# Side_ShortE.net
KiCad netlist of a schematic drawn in EAGLE
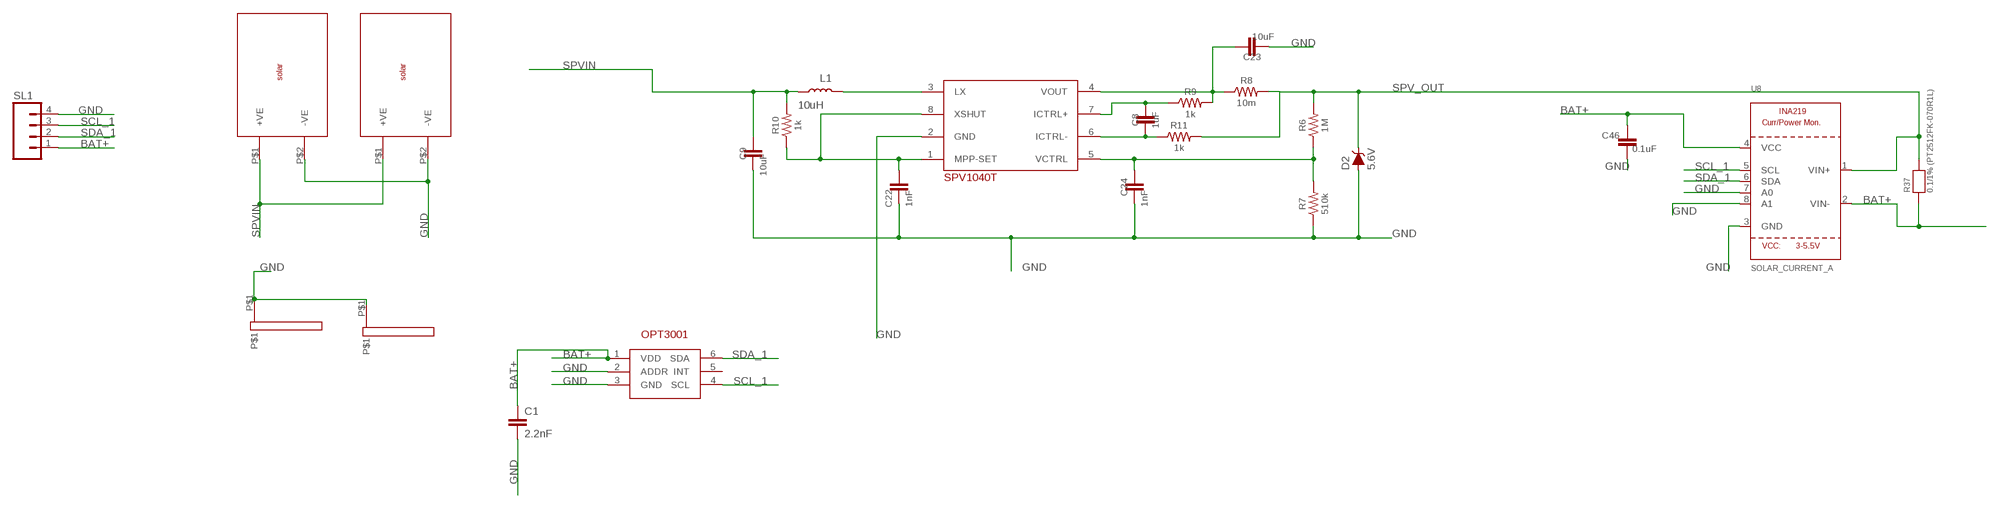
[diagram p0: schematic, sheet 1]

(export (version "E")
  (design (tool "Eeschema 10.0.6"))
  (components
    (comp (ref "C1")
      (value "2.2nF")
      (footprint "eagle-import:0603")
      (libsource (lib "eagle-import") (part "2.2NF/2200PF-0603-50V-10%"))
    )
    (comp (ref "C8")
      (value "1uF")
      (footprint "eagle-import:0603")
      (libsource (lib "eagle-import") (part "10UF-0603-6.3V-20%"))
    )
    (comp (ref "C9")
      (value "10uF")
      (footprint "eagle-import:0603")
      (libsource (lib "eagle-import") (part "10UF-0603-6.3V-20%"))
    )
    (comp (ref "C22")
      (value "1nF")
      (footprint "eagle-import:0603")
      (libsource (lib "eagle-import") (part "10UF-0603-6.3V-20%"))
    )
    (comp (ref "C23")
      (value "10uF")
      (footprint "eagle-import:0603")
      (libsource (lib "eagle-import") (part "10UF-0603-6.3V-20%"))
    )
    (comp (ref "C24")
      (value "1nF")
      (footprint "eagle-import:0603")
      (libsource (lib "eagle-import") (part "10UF-0603-6.3V-20%"))
    )
    (comp (ref "C46")
      (value "0.1uF")
      (footprint "eagle-import:0603")
      (libsource (lib "eagle-import") (part "10UF-0603-6.3V-20%"))
    )
    (comp (ref "D2")
      (value "5.6V")
      (footprint "eagle-import:SOD-323")
      (libsource (lib "eagle-import") (part "DIODE-ZENER-MMSZ5232BS"))
    )
    (comp (ref "L1")
      (value "10uH")
      (footprint "eagle-import:0603")
      (libsource (lib "eagle-import") (part "INDUCTOR-0603-33NH"))
    )
    (comp (ref "R6")
      (value "1M")
      (footprint "eagle-import:RES_0603")
      (fields
        (field (name "DIGIKEY_PART_NUMBER") "311-0.0GRTR-ND")
        (field (name "MANUFACTURER") "Yageo")
        (field (name "MPN") "RC0603JR-070RL")
        (field (name "CREATED_BY") "PCBLayout.com")
      )
      (libsource (lib "eagle-import") (part "RC0603JR-070RL"))
    )
    (comp (ref "R7")
      (value "510k")
      (footprint "eagle-import:RES_0603")
      (fields
        (field (name "DIGIKEY_PART_NUMBER") "311-0.0GRTR-ND")
        (field (name "MANUFACTURER") "Yageo")
        (field (name "MPN") "RC0603JR-070RL")
        (field (name "CREATED_BY") "PCBLayout.com")
      )
      (libsource (lib "eagle-import") (part "RC0603JR-070RL"))
    )
    (comp (ref "R8")
      (value "10m")
      (footprint "eagle-import:RES_0603")
      (fields
        (field (name "DIGIKEY_PART_NUMBER") "311-0.0GRTR-ND")
        (field (name "MANUFACTURER") "Yageo")
        (field (name "MPN") "RC0603JR-070RL")
        (field (name "CREATED_BY") "PCBLayout.com")
      )
      (libsource (lib "eagle-import") (part "RC0603JR-070RL"))
    )
    (comp (ref "R9")
      (value "1k")
      (footprint "eagle-import:RES_0603")
      (fields
        (field (name "DIGIKEY_PART_NUMBER") "311-0.0GRTR-ND")
        (field (name "MANUFACTURER") "Yageo")
        (field (name "MPN") "RC0603JR-070RL")
        (field (name "CREATED_BY") "PCBLayout.com")
      )
      (libsource (lib "eagle-import") (part "RC0603JR-070RL"))
    )
    (comp (ref "R10")
      (value "1k")
      (footprint "eagle-import:RES_0603")
      (fields
        (field (name "DIGIKEY_PART_NUMBER") "311-0.0GRTR-ND")
        (field (name "MANUFACTURER") "Yageo")
        (field (name "MPN") "RC0603JR-070RL")
        (field (name "CREATED_BY") "PCBLayout.com")
      )
      (libsource (lib "eagle-import") (part "RC0603JR-070RL"))
    )
    (comp (ref "R11")
      (value "1k")
      (footprint "eagle-import:RES_0603")
      (fields
        (field (name "DIGIKEY_PART_NUMBER") "311-0.0GRTR-ND")
        (field (name "MANUFACTURER") "Yageo")
        (field (name "MPN") "RC0603JR-070RL")
        (field (name "CREATED_BY") "PCBLayout.com")
      )
      (libsource (lib "eagle-import") (part "RC0603JR-070RL"))
    )
    (comp (ref "R37")
      (value "0.1/1% (PT2512FK-070R1L)")
      (footprint "eagle-import:2512")
      (libsource (lib "eagle-import") (part "RESISTOR2512"))
    )
    (comp (ref "SL1")
      (value "M04")
      (footprint "eagle-import:04P")
      (libsource (lib "eagle-import") (part "M04"))
    )
    (comp (ref "SPV_A")
      (value "SPV1040T_")
      (footprint "eagle-import:SOP65P640X120-8N")
      (libsource (lib "eagle-import") (part "SPV1040T_"))
    )
    (comp (ref "U$1")
      (value "16X2")
      (footprint "eagle-import:16X2")
      (libsource (lib "eagle-import") (part "16X2"))
    )
    (comp (ref "U$2")
      (value "16X2")
      (footprint "eagle-import:16X2")
      (libsource (lib "eagle-import") (part "16X2"))
    )
    (comp (ref "U$3")
      (value "SOLAR_50_5_2")
      (footprint "eagle-import:FOOT")
      (libsource (lib "eagle-import") (part "SOLAR_50_5_2"))
    )
    (comp (ref "U$4")
      (value "SOLAR_50_5_2")
      (footprint "eagle-import:FOOT")
      (libsource (lib "eagle-import") (part "SOLAR_50_5_2"))
    )
    (comp (ref "U1")
      (value "SON65P200X200X65-7N")
      (footprint "eagle-import:SON65P200X200X65-7N")
      (fields (field (name "MANUFACTURER") "Maxim Integrated"))
      (libsource (lib "eagle-import") (part "SON65P200X200X65-7N"))
    )
    (comp (ref "U8")
      (value "SOLAR_CURRENT_A")
      (footprint "eagle-import:SOT23-8")
      (libsource (lib "eagle-import") (part "INA219"))
    )
  )
  (nets
    (net (code "1") (name "/BAT+") (class "Default")
      (node (ref "C1") (pin "1") (pinfunction "1_1") (pintype "passive"))
      (node (ref "C46") (pin "1") (pinfunction "1_1") (pintype "passive"))
      (node (ref "R37") (pin "1") (pinfunction "1_1") (pintype "passive"))
      (node (ref "SL1") (pin "1") (pinfunction "1_1") (pintype "passive"))
      (node (ref "U1") (pin "1") (pinfunction "VDD_1") (pintype "bidirectional"))
      (node (ref "U8") (pin "2") (pinfunction "VIN-_2") (pintype "bidirectional"))
      (node (ref "U8") (pin "4") (pinfunction "VCC_4") (pintype "bidirectional"))
    )
    (net (code "2") (name "/GND") (class "Default")
      (node (ref "C1") (pin "2") (pinfunction "2_2") (pintype "passive"))
      (node (ref "C22") (pin "2") (pinfunction "2_2") (pintype "passive"))
      (node (ref "C23") (pin "2") (pinfunction "2_2") (pintype "passive"))
      (node (ref "C24") (pin "2") (pinfunction "2_2") (pintype "passive"))
      (node (ref "C46") (pin "2") (pinfunction "2_2") (pintype "passive"))
      (node (ref "C9") (pin "2") (pinfunction "2_2") (pintype "passive"))
      (node (ref "D2") (pin "A") (pinfunction "A_A") (pintype "passive"))
      (node (ref "R7") (pin "1") (pinfunction "1_1") (pintype "passive"))
      (node (ref "SL1") (pin "4") (pinfunction "4_4") (pintype "passive"))
      (node (ref "SPV_A") (pin "2") (pinfunction "GND_2") (pintype "bidirectional"))
      (node (ref "U$1") (pin "P$1") (pinfunction "P$1_P$1") (pintype "bidirectional"))
      (node (ref "U$2") (pin "P$1") (pinfunction "P$1_P$1") (pintype "bidirectional"))
      (node (ref "U$3") (pin "P$2") (pinfunction "-VE_P$2") (pintype "bidirectional"))
      (node (ref "U$4") (pin "P$2") (pinfunction "-VE_P$2") (pintype "bidirectional"))
      (node (ref "U1") (pin "2") (pinfunction "ADDR_2") (pintype "bidirectional"))
      (node (ref "U1") (pin "3") (pinfunction "GND_3") (pintype "bidirectional"))
      (node (ref "U8") (pin "3") (pinfunction "GND_3") (pintype "bidirectional"))
      (node (ref "U8") (pin "7") (pinfunction "A0_7") (pintype "bidirectional"))
      (node (ref "U8") (pin "8") (pinfunction "A1_8") (pintype "bidirectional"))
    )
    (net (code "3") (name "/SCL_1") (class "Default")
      (node (ref "SL1") (pin "3") (pinfunction "3_3") (pintype "passive"))
      (node (ref "U1") (pin "4") (pinfunction "SCL_4") (pintype "bidirectional"))
      (node (ref "U8") (pin "5") (pinfunction "SCL_5") (pintype "bidirectional"))
    )
    (net (code "4") (name "/SDA_1") (class "Default")
      (node (ref "SL1") (pin "2") (pinfunction "2_2") (pintype "passive"))
      (node (ref "U1") (pin "6") (pinfunction "SDA_6") (pintype "bidirectional"))
      (node (ref "U8") (pin "6") (pinfunction "SDA_6") (pintype "bidirectional"))
    )
    (net (code "5") (name "/SPVIN") (class "Default")
      (node (ref "C9") (pin "1") (pinfunction "1_1") (pintype "passive"))
      (node (ref "L1") (pin "1") (pinfunction "1_1") (pintype "passive"))
      (node (ref "R10") (pin "2") (pinfunction "2_2") (pintype "passive"))
      (node (ref "U$3") (pin "P$1") (pinfunction "+VE_P$1") (pintype "bidirectional"))
      (node (ref "U$4") (pin "P$1") (pinfunction "+VE_P$1") (pintype "bidirectional"))
    )
    (net (code "6") (name "/SPV_OUT") (class "Default")
      (node (ref "D2") (pin "C") (pinfunction "C_C") (pintype "passive"))
      (node (ref "R11") (pin "2") (pinfunction "2_2") (pintype "passive"))
      (node (ref "R37") (pin "2") (pinfunction "2_2") (pintype "passive"))
      (node (ref "R6") (pin "2") (pinfunction "2_2") (pintype "passive"))
      (node (ref "R8") (pin "2") (pinfunction "2_2") (pintype "passive"))
      (node (ref "U8") (pin "1") (pinfunction "VIN+_1") (pintype "bidirectional"))
    )
    (net (code "7") (name "Net-(SPV_A-ICTRL+)") (class "Default")
      (node (ref "C8") (pin "1") (pinfunction "1_1") (pintype "passive"))
      (node (ref "R9") (pin "1") (pinfunction "1_1") (pintype "passive"))
      (node (ref "SPV_A") (pin "7") (pinfunction "ICTRL+_7") (pintype "bidirectional"))
    )
    (net (code "8") (name "Net-(SPV_A-ICTRL-)") (class "Default")
      (node (ref "C8") (pin "2") (pinfunction "2_2") (pintype "passive"))
      (node (ref "R11") (pin "1") (pinfunction "1_1") (pintype "passive"))
      (node (ref "SPV_A") (pin "6") (pinfunction "ICTRL-_6") (pintype "bidirectional"))
    )
    (net (code "9") (name "Net-(SPV_A-LX)") (class "Default")
      (node (ref "L1") (pin "2") (pinfunction "2_2") (pintype "passive"))
      (node (ref "SPV_A") (pin "3") (pinfunction "LX_3") (pintype "bidirectional"))
    )
    (net (code "10") (name "Net-(SPV_A-MPP-SET)") (class "Default")
      (node (ref "C22") (pin "1") (pinfunction "1_1") (pintype "passive"))
      (node (ref "R10") (pin "1") (pinfunction "1_1") (pintype "passive"))
      (node (ref "SPV_A") (pin "1") (pinfunction "MPP-SET_1") (pintype "bidirectional"))
      (node (ref "SPV_A") (pin "8") (pinfunction "XSHUT_8") (pintype "bidirectional"))
    )
    (net (code "11") (name "Net-(SPV_A-VCTRL)") (class "Default")
      (node (ref "C24") (pin "1") (pinfunction "1_1") (pintype "passive"))
      (node (ref "R6") (pin "1") (pinfunction "1_1") (pintype "passive"))
      (node (ref "R7") (pin "2") (pinfunction "2_2") (pintype "passive"))
      (node (ref "SPV_A") (pin "5") (pinfunction "VCTRL_5") (pintype "bidirectional"))
    )
    (net (code "12") (name "Net-(SPV_A-VOUT)") (class "Default")
      (node (ref "C23") (pin "1") (pinfunction "1_1") (pintype "passive"))
      (node (ref "R8") (pin "1") (pinfunction "1_1") (pintype "passive"))
      (node (ref "R9") (pin "2") (pinfunction "2_2") (pintype "passive"))
      (node (ref "SPV_A") (pin "4") (pinfunction "VOUT_4") (pintype "bidirectional"))
    )
    (net (code "13") (name "unconnected-(U1-INT-Pad5)") (class "Default")
      (node (ref "U1") (pin "5") (pinfunction "INT_5") (pintype "bidirectional"))
    )
  )
)
